# mosfet-shield-v2.net
KiCad netlist of a schematic drawn in EAGLE
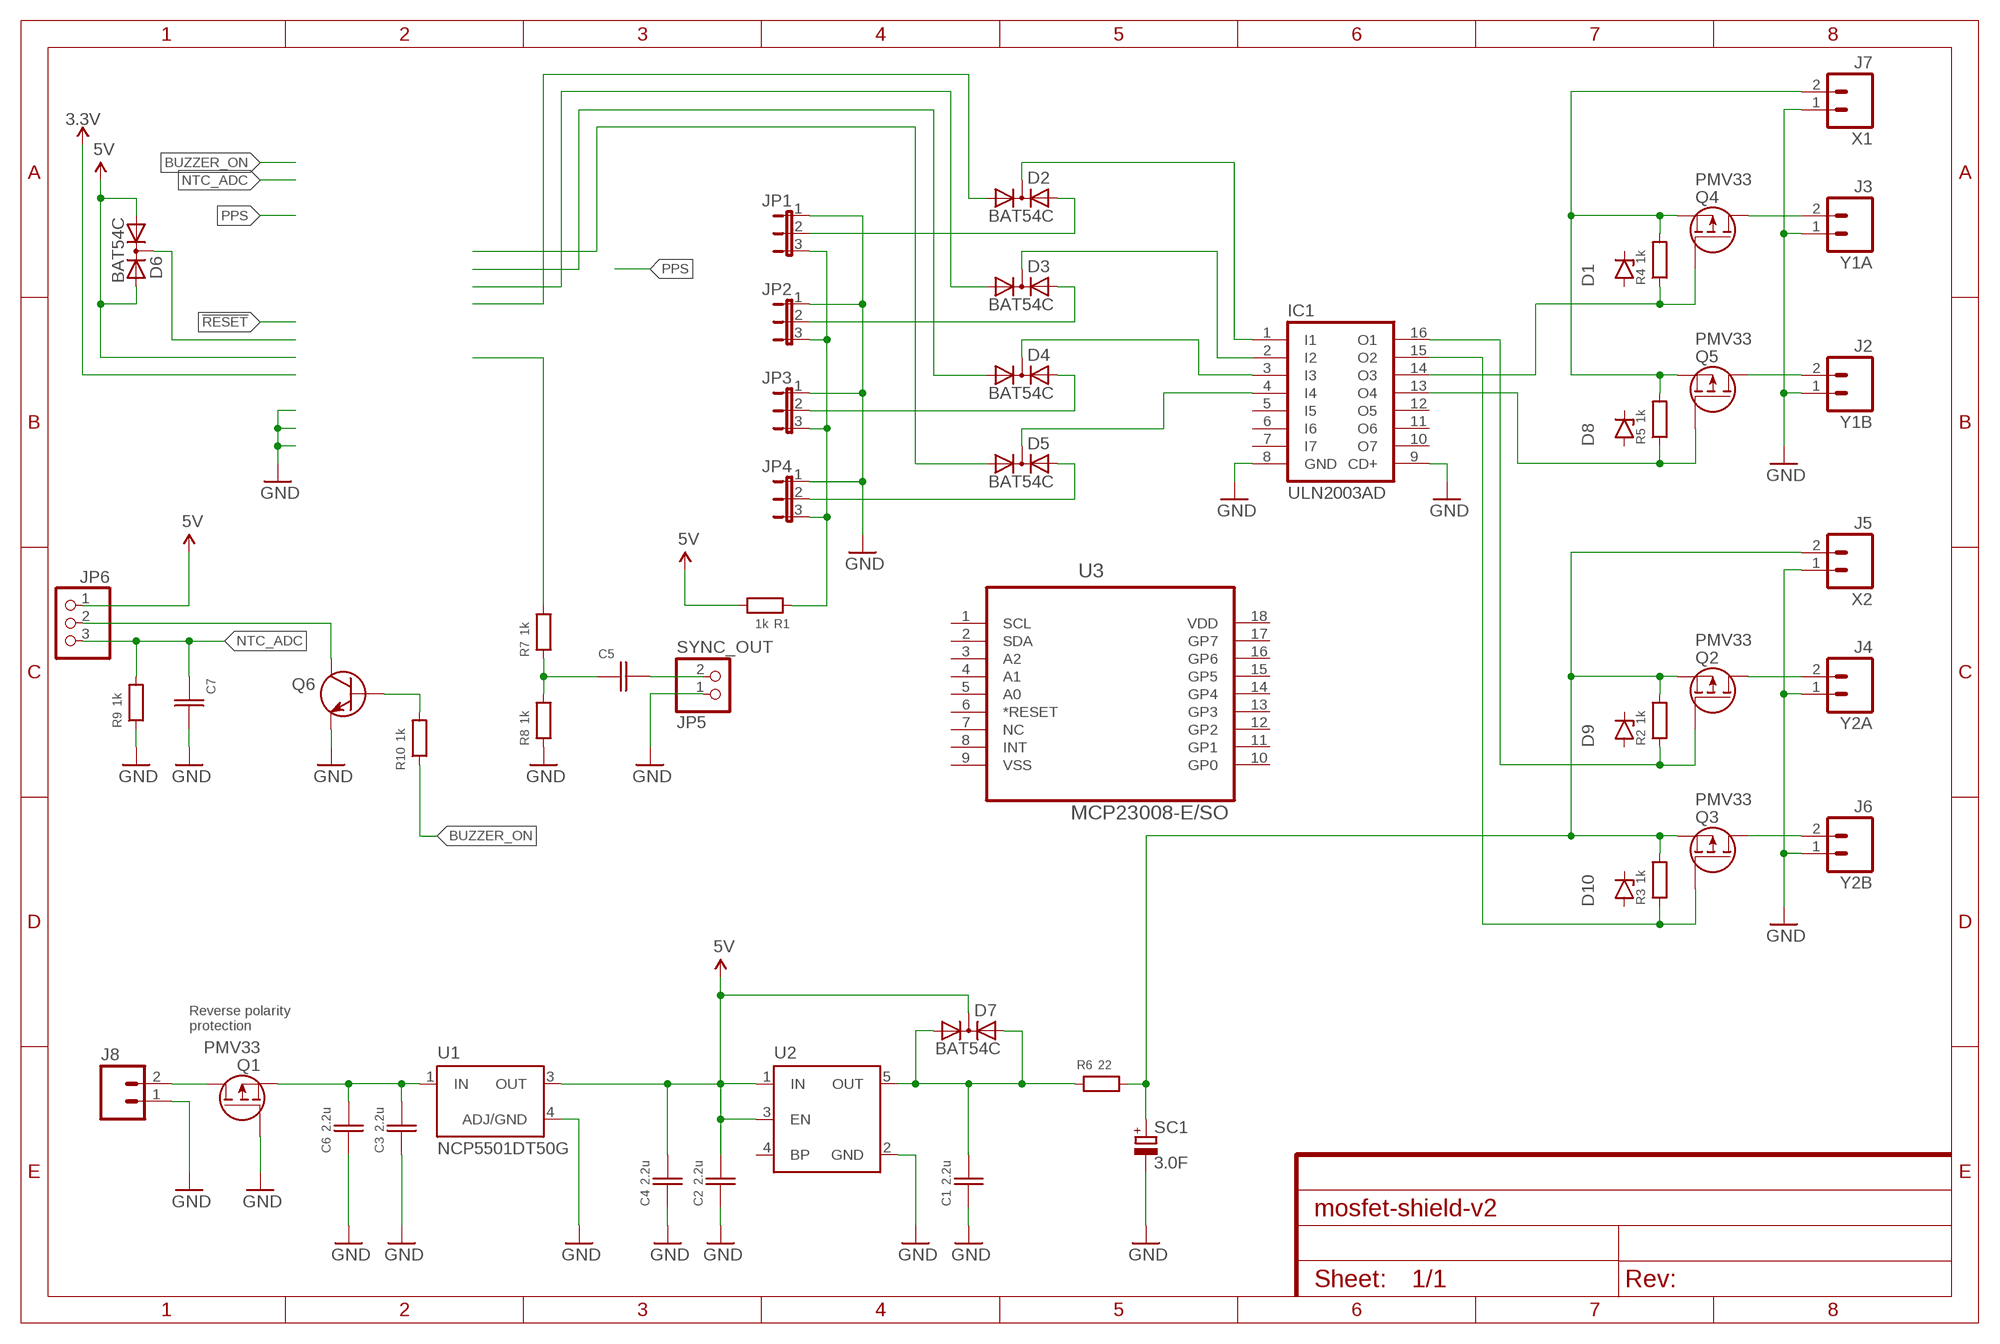
[diagram p0: schematic, sheet 1]

(export (version "E")
  (design (tool "Eeschema 10.0.6"))
  (components
    (comp (ref "C1")
      (value "2.2u")
      (footprint "eagle-import:C1206")
      (libsource (lib "eagle-import") (part "CAPACITOR_NPOL-1206"))
    )
    (comp (ref "C2")
      (value "2.2u")
      (footprint "eagle-import:C1206")
      (libsource (lib "eagle-import") (part "CAPACITOR_NPOL-1206"))
    )
    (comp (ref "C3")
      (value "2.2u")
      (footprint "eagle-import:C1206")
      (libsource (lib "eagle-import") (part "CAPACITOR_NPOL-1206"))
    )
    (comp (ref "C4")
      (value "2.2u")
      (footprint "eagle-import:C1206")
      (libsource (lib "eagle-import") (part "CAPACITOR_NPOL-1206"))
    )
    (comp (ref "C5")
      (value "CAPACITOR_NPOL-0603")
      (footprint "eagle-import:C603")
      (libsource (lib "eagle-import") (part "CAPACITOR_NPOL-0603"))
    )
    (comp (ref "C6")
      (value "2.2u")
      (footprint "eagle-import:C1206")
      (libsource (lib "eagle-import") (part "CAPACITOR_NPOL-1206"))
    )
    (comp (ref "C7")
      (value "CAPACITOR_NPOL-0603")
      (footprint "eagle-import:C603")
      (libsource (lib "eagle-import") (part "CAPACITOR_NPOL-0603"))
    )
    (comp (ref "D1")
      (value "DIODE-ZENER-SOD80")
      (footprint "eagle-import:SOD80")
      (libsource (lib "eagle-import") (part "DIODE-ZENER-SOD80"))
    )
    (comp (ref "D2")
      (value "BAT54C")
      (footprint "eagle-import:SOT23")
      (libsource (lib "eagle-import") (part "DIODE-2AC|CASOT23"))
    )
    (comp (ref "D3")
      (value "BAT54C")
      (footprint "eagle-import:SOT23")
      (libsource (lib "eagle-import") (part "DIODE-2AC|CASOT23"))
    )
    (comp (ref "D4")
      (value "BAT54C")
      (footprint "eagle-import:SOT23")
      (libsource (lib "eagle-import") (part "DIODE-2AC|CASOT23"))
    )
    (comp (ref "D5")
      (value "BAT54C")
      (footprint "eagle-import:SOT23")
      (libsource (lib "eagle-import") (part "DIODE-2AC|CASOT23"))
    )
    (comp (ref "D6")
      (value "BAT54C")
      (footprint "eagle-import:SOT23")
      (libsource (lib "eagle-import") (part "DIODE-2AC|CASOT23"))
    )
    (comp (ref "D7")
      (value "BAT54C")
      (footprint "eagle-import:SOT23")
      (libsource (lib "eagle-import") (part "DIODE-2AC|CASOT23"))
    )
    (comp (ref "D8")
      (value "DIODE-ZENER-SOD80")
      (footprint "eagle-import:SOD80")
      (libsource (lib "eagle-import") (part "DIODE-ZENER-SOD80"))
    )
    (comp (ref "D9")
      (value "DIODE-ZENER-SOD80")
      (footprint "eagle-import:SOD80")
      (libsource (lib "eagle-import") (part "DIODE-ZENER-SOD80"))
    )
    (comp (ref "D10")
      (value "DIODE-ZENER-SOD80")
      (footprint "eagle-import:SOD80")
      (libsource (lib "eagle-import") (part "DIODE-ZENER-SOD80"))
    )
    (comp (ref "IC1")
      (value "ULN2003AD")
      (footprint "eagle-import:SO16")
      (libsource (lib "eagle-import") (part "ULN2003AD"))
    )
    (comp (ref "J2")
      (value "Y1B")
      (footprint "eagle-import:SCREWTERMINAL-3.5MM-2")
      (libsource (lib "eagle-import") (part "M023.5MM"))
    )
    (comp (ref "J3")
      (value "Y1A")
      (footprint "eagle-import:SCREWTERMINAL-3.5MM-2")
      (libsource (lib "eagle-import") (part "M023.5MM"))
    )
    (comp (ref "J4")
      (value "Y2A")
      (footprint "eagle-import:SCREWTERMINAL-3.5MM-2")
      (libsource (lib "eagle-import") (part "M023.5MM"))
    )
    (comp (ref "J5")
      (value "X2")
      (footprint "eagle-import:SCREWTERMINAL-3.5MM-2")
      (libsource (lib "eagle-import") (part "M023.5MM"))
    )
    (comp (ref "J6")
      (value "Y2B")
      (footprint "eagle-import:SCREWTERMINAL-3.5MM-2")
      (libsource (lib "eagle-import") (part "M023.5MM"))
    )
    (comp (ref "J7")
      (value "X1")
      (footprint "eagle-import:SCREWTERMINAL-3.5MM-2")
      (libsource (lib "eagle-import") (part "M023.5MM"))
    )
    (comp (ref "J8")
      (value "M023.5MM")
      (footprint "eagle-import:SCREWTERMINAL-3.5MM-2")
      (libsource (lib "eagle-import") (part "M023.5MM"))
    )
    (comp (ref "JP1")
      (value "JP2E")
      (footprint "eagle-import:JP2")
      (libsource (lib "eagle-import") (part "JP2E"))
    )
    (comp (ref "JP2")
      (value "JP2E")
      (footprint "eagle-import:JP2")
      (libsource (lib "eagle-import") (part "JP2E"))
    )
    (comp (ref "JP3")
      (value "JP2E")
      (footprint "eagle-import:JP2")
      (libsource (lib "eagle-import") (part "JP2E"))
    )
    (comp (ref "JP4")
      (value "JP2E")
      (footprint "eagle-import:JP2")
      (libsource (lib "eagle-import") (part "JP2E"))
    )
    (comp (ref "JP5")
      (value "SYNC_OUT")
      (footprint "eagle-import:1X02")
      (libsource (lib "eagle-import") (part "PINHD-1X2"))
    )
    (comp (ref "JP6")
      (value "PINHD-1X3")
      (footprint "eagle-import:1X03")
      (libsource (lib "eagle-import") (part "PINHD-1X3"))
    )
    (comp (ref "Q1")
      (value "PMV33")
      (footprint "eagle-import:SOT23-3")
      (libsource (lib "eagle-import") (part "MOSFET-P-SOT23-3"))
    )
    (comp (ref "Q2")
      (value "PMV33")
      (footprint "eagle-import:SOT23-3")
      (libsource (lib "eagle-import") (part "MOSFET-P-SOT23-3"))
    )
    (comp (ref "Q3")
      (value "PMV33")
      (footprint "eagle-import:SOT23-3")
      (libsource (lib "eagle-import") (part "MOSFET-P-SOT23-3"))
    )
    (comp (ref "Q4")
      (value "PMV33")
      (footprint "eagle-import:SOT23-3")
      (libsource (lib "eagle-import") (part "MOSFET-P-SOT23-3"))
    )
    (comp (ref "Q5")
      (value "PMV33")
      (footprint "eagle-import:SOT23-3")
      (libsource (lib "eagle-import") (part "MOSFET-P-SOT23-3"))
    )
    (comp (ref "Q6")
      (value "BJT-NPN-SOT23-3")
      (footprint "eagle-import:SOT23-3")
      (libsource (lib "eagle-import") (part "BJT-NPN-SOT23-3"))
    )
    (comp (ref "R1")
      (value "1k")
      (footprint "eagle-import:R0603")
      (libsource (lib "eagle-import") (part "RESISTOR-0603"))
    )
    (comp (ref "R2")
      (value "1k")
      (footprint "eagle-import:R0603")
      (libsource (lib "eagle-import") (part "RESISTOR-0603"))
    )
    (comp (ref "R3")
      (value "1k")
      (footprint "eagle-import:R0603")
      (libsource (lib "eagle-import") (part "RESISTOR-0603"))
    )
    (comp (ref "R4")
      (value "1k")
      (footprint "eagle-import:R0603")
      (libsource (lib "eagle-import") (part "RESISTOR-0603"))
    )
    (comp (ref "R5")
      (value "1k")
      (footprint "eagle-import:R0603")
      (libsource (lib "eagle-import") (part "RESISTOR-0603"))
    )
    (comp (ref "R6")
      (value "22")
      (footprint "eagle-import:R0603")
      (libsource (lib "eagle-import") (part "RESISTOR-0603"))
    )
    (comp (ref "R7")
      (value "1k")
      (footprint "eagle-import:R0603")
      (libsource (lib "eagle-import") (part "RESISTOR-0603"))
    )
    (comp (ref "R8")
      (value "1k")
      (footprint "eagle-import:R0603")
      (libsource (lib "eagle-import") (part "RESISTOR-0603"))
    )
    (comp (ref "R9")
      (value "1k")
      (footprint "eagle-import:R0603")
      (libsource (lib "eagle-import") (part "RESISTOR-0603"))
    )
    (comp (ref "R10")
      (value "1k")
      (footprint "eagle-import:R0603")
      (libsource (lib "eagle-import") (part "RESISTOR-0603"))
    )
    (comp (ref "SC1")
      (value "3.0F")
      (footprint "eagle-import:E3,5-8")
      (libsource (lib "eagle-import") (part "CPOL-EUE3.5-8"))
    )
    (comp (ref "U1")
      (value "NCP5501DT50G")
      (footprint "eagle-import:DPAK")
      (libsource (lib "eagle-import") (part "VREG-3PIN-DPAK"))
    )
    (comp (ref "U2")
      (value "VREG-5PIN-SOT23")
      (footprint "eagle-import:SOT23-5")
      (libsource (lib "eagle-import") (part "VREG-5PIN-SOT23"))
    )
    (comp (ref "U3")
      (value "MCP23008-E/SO")
      (footprint "eagle-import:SOIC127P1030X265-18N")
      (libsource (lib "eagle-import") (part "MCP23008-E/SO"))
    )
  )
  (nets
    (net (code "1") (name "/VDD") (class "Default")
      (node (ref "U3") (pin "18") (pinfunction "VDD_18") (pintype "power_in"))
    )
    (net (code "4") (name "5V") (class "Default")
      (node (ref "C2") (pin "2") (pinfunction "2_2") (pintype "passive"))
      (node (ref "C4") (pin "2") (pinfunction "2_2") (pintype "passive"))
      (node (ref "D6") (pin "1") (pinfunction "A1_1") (pintype "passive"))
      (node (ref "D6") (pin "2") (pinfunction "A2_2") (pintype "passive"))
      (node (ref "D7") (pin "3") (pinfunction "C_3") (pintype "passive"))
      (node (ref "JP6") (pin "1") (pinfunction "1_1") (pintype "passive"))
      (node (ref "R1") (pin "2") (pinfunction "2_2") (pintype "passive"))
      (node (ref "U1") (pin "3") (pinfunction "OUT_3") (pintype "bidirectional"))
      (node (ref "U2") (pin "1") (pinfunction "IN_1") (pintype "bidirectional"))
      (node (ref "U2") (pin "3") (pinfunction "EN_3") (pintype "bidirectional"))
    )
    (net (code "5") (name "BUZZER_ON") (class "Default")
      (node (ref "R10") (pin "1") (pinfunction "1_1") (pintype "passive"))
    )
    (net (code "6") (name "GND") (class "Default")
      (node (ref "C1") (pin "1") (pinfunction "1_1") (pintype "passive"))
      (node (ref "C2") (pin "1") (pinfunction "1_1") (pintype "passive"))
      (node (ref "C3") (pin "1") (pinfunction "1_1") (pintype "passive"))
      (node (ref "C4") (pin "1") (pinfunction "1_1") (pintype "passive"))
      (node (ref "C6") (pin "1") (pinfunction "1_1") (pintype "passive"))
      (node (ref "C7") (pin "2") (pinfunction "2_2") (pintype "passive"))
      (node (ref "IC1") (pin "8") (pinfunction "GND_8") (pintype "power_in"))
      (node (ref "IC1") (pin "9") (pinfunction "CD+_9") (pintype "passive"))
      (node (ref "J2") (pin "1") (pinfunction "1_1") (pintype "passive"))
      (node (ref "J3") (pin "1") (pinfunction "1_1") (pintype "passive"))
      (node (ref "J4") (pin "1") (pinfunction "1_1") (pintype "passive"))
      (node (ref "J5") (pin "1") (pinfunction "1_1") (pintype "passive"))
      (node (ref "J6") (pin "1") (pinfunction "1_1") (pintype "passive"))
      (node (ref "J7") (pin "1") (pinfunction "1_1") (pintype "passive"))
      (node (ref "J8") (pin "1") (pinfunction "1_1") (pintype "passive"))
      (node (ref "JP1") (pin "1") (pinfunction "1_1") (pintype "passive"))
      (node (ref "JP2") (pin "1") (pinfunction "1_1") (pintype "passive"))
      (node (ref "JP3") (pin "1") (pinfunction "1_1") (pintype "passive"))
      (node (ref "JP4") (pin "1") (pinfunction "1_1") (pintype "passive"))
      (node (ref "JP5") (pin "1") (pinfunction "1_1") (pintype "passive"))
      (node (ref "Q1") (pin "1") (pinfunction "G_1") (pintype "passive"))
      (node (ref "Q6") (pin "2") (pinfunction "E_2") (pintype "passive"))
      (node (ref "R8") (pin "1") (pinfunction "1_1") (pintype "passive"))
      (node (ref "R9") (pin "1") (pinfunction "1_1") (pintype "passive"))
      (node (ref "SC1") (pin "-") (pinfunction "-_-") (pintype "passive"))
      (node (ref "U1") (pin "4") (pinfunction "ADJ/GND_4") (pintype "bidirectional"))
      (node (ref "U2") (pin "2") (pinfunction "GND_2") (pintype "bidirectional"))
    )
    (net (code "7") (name "NTC_ADC") (class "Default")
      (node (ref "C7") (pin "1") (pinfunction "1_1") (pintype "passive"))
      (node (ref "JP6") (pin "3") (pinfunction "3_3") (pintype "passive"))
      (node (ref "R9") (pin "2") (pinfunction "2_2") (pintype "passive"))
    )
    (net (code "8") (name "Net-(C5-Pad1)") (class "Default")
      (node (ref "C5") (pin "1") (pinfunction "1_1") (pintype "passive"))
      (node (ref "R7") (pin "1") (pinfunction "1_1") (pintype "passive"))
      (node (ref "R8") (pin "2") (pinfunction "2_2") (pintype "passive"))
    )
    (net (code "9") (name "Net-(C5-Pad2)") (class "Default")
      (node (ref "C5") (pin "2") (pinfunction "2_2") (pintype "passive"))
      (node (ref "JP5") (pin "2") (pinfunction "2_2") (pintype "passive"))
    )
    (net (code "10") (name "Net-(D2-A2)") (class "Default")
      (node (ref "D2") (pin "2") (pinfunction "A2_2") (pintype "passive"))
      (node (ref "JP1") (pin "2") (pinfunction "2_2") (pintype "passive"))
    )
    (net (code "11") (name "Net-(D2-C)") (class "Default")
      (node (ref "D2") (pin "3") (pinfunction "C_3") (pintype "passive"))
      (node (ref "IC1") (pin "1") (pinfunction "I1_1") (pintype "input"))
    )
    (net (code "12") (name "Net-(D3-A2)") (class "Default")
      (node (ref "D3") (pin "2") (pinfunction "A2_2") (pintype "passive"))
      (node (ref "JP2") (pin "2") (pinfunction "2_2") (pintype "passive"))
    )
    (net (code "13") (name "Net-(D3-C)") (class "Default")
      (node (ref "D3") (pin "3") (pinfunction "C_3") (pintype "passive"))
      (node (ref "IC1") (pin "2") (pinfunction "I2_2") (pintype "input"))
    )
    (net (code "14") (name "Net-(D4-A2)") (class "Default")
      (node (ref "D4") (pin "2") (pinfunction "A2_2") (pintype "passive"))
      (node (ref "JP3") (pin "2") (pinfunction "2_2") (pintype "passive"))
    )
    (net (code "15") (name "Net-(D4-C)") (class "Default")
      (node (ref "D4") (pin "3") (pinfunction "C_3") (pintype "passive"))
      (node (ref "IC1") (pin "3") (pinfunction "I3_3") (pintype "input"))
    )
    (net (code "16") (name "Net-(D5-A2)") (class "Default")
      (node (ref "D5") (pin "2") (pinfunction "A2_2") (pintype "passive"))
      (node (ref "JP4") (pin "2") (pinfunction "2_2") (pintype "passive"))
    )
    (net (code "17") (name "Net-(D5-C)") (class "Default")
      (node (ref "D5") (pin "3") (pinfunction "C_3") (pintype "passive"))
      (node (ref "IC1") (pin "4") (pinfunction "I4_4") (pintype "input"))
    )
    (net (code "18") (name "Net-(D7-A1)") (class "Default")
      (node (ref "C1") (pin "2") (pinfunction "2_2") (pintype "passive"))
      (node (ref "D7") (pin "1") (pinfunction "A1_1") (pintype "passive"))
      (node (ref "D7") (pin "2") (pinfunction "A2_2") (pintype "passive"))
      (node (ref "R6") (pin "1") (pinfunction "1_1") (pintype "passive"))
      (node (ref "U2") (pin "5") (pinfunction "OUT_5") (pintype "bidirectional"))
    )
    (net (code "19") (name "Net-(IC1-O1)") (class "Default")
      (node (ref "IC1") (pin "16") (pinfunction "O1_16") (pintype "open_collector"))
      (node (ref "Q2") (pin "1") (pinfunction "G_1") (pintype "passive"))
      (node (ref "R2") (pin "1") (pinfunction "1_1") (pintype "passive"))
    )
    (net (code "20") (name "Net-(IC1-O2)") (class "Default")
      (node (ref "IC1") (pin "15") (pinfunction "O2_15") (pintype "open_collector"))
      (node (ref "Q3") (pin "1") (pinfunction "G_1") (pintype "passive"))
      (node (ref "R3") (pin "1") (pinfunction "1_1") (pintype "passive"))
    )
    (net (code "21") (name "Net-(IC1-O3)") (class "Default")
      (node (ref "IC1") (pin "14") (pinfunction "O3_14") (pintype "open_collector"))
      (node (ref "Q4") (pin "1") (pinfunction "G_1") (pintype "passive"))
      (node (ref "R4") (pin "1") (pinfunction "1_1") (pintype "passive"))
    )
    (net (code "22") (name "Net-(IC1-O4)") (class "Default")
      (node (ref "IC1") (pin "13") (pinfunction "O4_13") (pintype "open_collector"))
      (node (ref "Q5") (pin "1") (pinfunction "G_1") (pintype "passive"))
      (node (ref "R5") (pin "1") (pinfunction "1_1") (pintype "passive"))
    )
    (net (code "23") (name "Net-(JP1-Pad3)") (class "Default")
      (node (ref "JP1") (pin "3") (pinfunction "3_3") (pintype "passive"))
      (node (ref "JP2") (pin "3") (pinfunction "3_3") (pintype "passive"))
      (node (ref "JP3") (pin "3") (pinfunction "3_3") (pintype "passive"))
      (node (ref "JP4") (pin "3") (pinfunction "3_3") (pintype "passive"))
      (node (ref "R1") (pin "1") (pinfunction "1_1") (pintype "passive"))
    )
    (net (code "24") (name "Net-(Q1-D)") (class "Default")
      (node (ref "J8") (pin "2") (pinfunction "2_2") (pintype "passive"))
      (node (ref "Q1") (pin "3") (pinfunction "D_3") (pintype "passive"))
    )
    (net (code "25") (name "Net-(Q1-S)") (class "Default")
      (node (ref "C3") (pin "2") (pinfunction "2_2") (pintype "passive"))
      (node (ref "C6") (pin "2") (pinfunction "2_2") (pintype "passive"))
      (node (ref "Q1") (pin "2") (pinfunction "S_2") (pintype "passive"))
      (node (ref "U1") (pin "1") (pinfunction "IN_1") (pintype "bidirectional"))
    )
    (net (code "26") (name "Net-(Q2-D)") (class "Default")
      (node (ref "J4") (pin "2") (pinfunction "2_2") (pintype "passive"))
      (node (ref "Q2") (pin "3") (pinfunction "D_3") (pintype "passive"))
    )
    (net (code "27") (name "Net-(Q2-S)") (class "Default")
      (node (ref "J5") (pin "2") (pinfunction "2_2") (pintype "passive"))
      (node (ref "Q2") (pin "2") (pinfunction "S_2") (pintype "passive"))
      (node (ref "Q3") (pin "2") (pinfunction "S_2") (pintype "passive"))
      (node (ref "R2") (pin "2") (pinfunction "2_2") (pintype "passive"))
      (node (ref "R3") (pin "2") (pinfunction "2_2") (pintype "passive"))
      (node (ref "R6") (pin "2") (pinfunction "2_2") (pintype "passive"))
      (node (ref "SC1") (pin "+") (pinfunction "+_+") (pintype "passive"))
    )
    (net (code "28") (name "Net-(Q3-D)") (class "Default")
      (node (ref "J6") (pin "2") (pinfunction "2_2") (pintype "passive"))
      (node (ref "Q3") (pin "3") (pinfunction "D_3") (pintype "passive"))
    )
    (net (code "29") (name "Net-(Q4-D)") (class "Default")
      (node (ref "J3") (pin "2") (pinfunction "2_2") (pintype "passive"))
      (node (ref "Q4") (pin "3") (pinfunction "D_3") (pintype "passive"))
    )
    (net (code "30") (name "Net-(Q4-S)") (class "Default")
      (node (ref "J7") (pin "2") (pinfunction "2_2") (pintype "passive"))
      (node (ref "Q4") (pin "2") (pinfunction "S_2") (pintype "passive"))
      (node (ref "Q5") (pin "2") (pinfunction "S_2") (pintype "passive"))
      (node (ref "R4") (pin "2") (pinfunction "2_2") (pintype "passive"))
      (node (ref "R5") (pin "2") (pinfunction "2_2") (pintype "passive"))
    )
    (net (code "31") (name "Net-(Q5-D)") (class "Default")
      (node (ref "J2") (pin "2") (pinfunction "2_2") (pintype "passive"))
      (node (ref "Q5") (pin "3") (pinfunction "D_3") (pintype "passive"))
    )
    (net (code "32") (name "Net-(Q6-B)") (class "Default")
      (node (ref "Q6") (pin "1") (pinfunction "B_1") (pintype "passive"))
      (node (ref "R10") (pin "2") (pinfunction "2_2") (pintype "passive"))
    )
    (net (code "33") (name "Net-(Q6-C)") (class "Default")
      (node (ref "JP6") (pin "2") (pinfunction "2_2") (pintype "passive"))
      (node (ref "Q6") (pin "3") (pinfunction "C_3") (pintype "passive"))
    )
    (net (code "35") (name "unconnected-(D1-PadA)") (class "Default")
      (node (ref "D1") (pin "A") (pinfunction "A_A") (pintype "passive"))
    )
    (net (code "36") (name "unconnected-(D1-PadC)") (class "Default")
      (node (ref "D1") (pin "C") (pinfunction "C_C") (pintype "passive"))
    )
    (net (code "37") (name "unconnected-(D2-A1-Pad1)") (class "Default")
      (node (ref "D2") (pin "1") (pinfunction "A1_1") (pintype "passive"))
    )
    (net (code "38") (name "unconnected-(D3-A1-Pad1)") (class "Default")
      (node (ref "D3") (pin "1") (pinfunction "A1_1") (pintype "passive"))
    )
    (net (code "39") (name "unconnected-(D4-A1-Pad1)") (class "Default")
      (node (ref "D4") (pin "1") (pinfunction "A1_1") (pintype "passive"))
    )
    (net (code "40") (name "unconnected-(D5-A1-Pad1)") (class "Default")
      (node (ref "D5") (pin "1") (pinfunction "A1_1") (pintype "passive"))
    )
    (net (code "41") (name "unconnected-(D6-C-Pad3)") (class "Default")
      (node (ref "D6") (pin "3") (pinfunction "C_3") (pintype "passive"))
    )
    (net (code "42") (name "unconnected-(D8-PadA)") (class "Default")
      (node (ref "D8") (pin "A") (pinfunction "A_A") (pintype "passive"))
    )
    (net (code "43") (name "unconnected-(D8-PadC)") (class "Default")
      (node (ref "D8") (pin "C") (pinfunction "C_C") (pintype "passive"))
    )
    (net (code "44") (name "unconnected-(D9-PadA)") (class "Default")
      (node (ref "D9") (pin "A") (pinfunction "A_A") (pintype "passive"))
    )
    (net (code "45") (name "unconnected-(D9-PadC)") (class "Default")
      (node (ref "D9") (pin "C") (pinfunction "C_C") (pintype "passive"))
    )
    (net (code "46") (name "unconnected-(D10-PadA)") (class "Default")
      (node (ref "D10") (pin "A") (pinfunction "A_A") (pintype "passive"))
    )
    (net (code "47") (name "unconnected-(D10-PadC)") (class "Default")
      (node (ref "D10") (pin "C") (pinfunction "C_C") (pintype "passive"))
    )
    (net (code "48") (name "unconnected-(IC1-I5-Pad5)") (class "Default")
      (node (ref "IC1") (pin "5") (pinfunction "I5_5") (pintype "input"))
    )
    (net (code "49") (name "unconnected-(IC1-I6-Pad6)") (class "Default")
      (node (ref "IC1") (pin "6") (pinfunction "I6_6") (pintype "input"))
    )
    (net (code "50") (name "unconnected-(IC1-I7-Pad7)") (class "Default")
      (node (ref "IC1") (pin "7") (pinfunction "I7_7") (pintype "input"))
    )
    (net (code "51") (name "unconnected-(IC1-O5-Pad12)") (class "Default")
      (node (ref "IC1") (pin "12") (pinfunction "O5_12") (pintype "open_collector"))
    )
    (net (code "52") (name "unconnected-(IC1-O6-Pad11)") (class "Default")
      (node (ref "IC1") (pin "11") (pinfunction "O6_11") (pintype "open_collector"))
    )
    (net (code "53") (name "unconnected-(IC1-O7-Pad10)") (class "Default")
      (node (ref "IC1") (pin "10") (pinfunction "O7_10") (pintype "open_collector"))
    )
    (net (code "54") (name "unconnected-(R7-Pad2)") (class "Default")
      (node (ref "R7") (pin "2") (pinfunction "2_2") (pintype "passive"))
    )
    (net (code "55") (name "unconnected-(U2-BP-Pad4)") (class "Default")
      (node (ref "U2") (pin "4") (pinfunction "BP_4") (pintype "bidirectional"))
    )
    (net (code "56") (name "unconnected-(U3-*RESET-Pad6)") (class "Default")
      (node (ref "U3") (pin "6") (pinfunction "*RESET_6") (pintype "input"))
    )
    (net (code "57") (name "unconnected-(U3-A0-Pad5)") (class "Default")
      (node (ref "U3") (pin "5") (pinfunction "A0_5") (pintype "input"))
    )
    (net (code "58") (name "unconnected-(U3-A1-Pad4)") (class "Default")
      (node (ref "U3") (pin "4") (pinfunction "A1_4") (pintype "input"))
    )
    (net (code "59") (name "unconnected-(U3-A2-Pad3)") (class "Default")
      (node (ref "U3") (pin "3") (pinfunction "A2_3") (pintype "passive"))
    )
    (net (code "60") (name "unconnected-(U3-GP0-Pad10)") (class "Default")
      (node (ref "U3") (pin "10") (pinfunction "GP0_10") (pintype "passive"))
    )
    (net (code "61") (name "unconnected-(U3-GP1-Pad11)") (class "Default")
      (node (ref "U3") (pin "11") (pinfunction "GP1_11") (pintype "passive"))
    )
    (net (code "62") (name "unconnected-(U3-GP2-Pad12)") (class "Default")
      (node (ref "U3") (pin "12") (pinfunction "GP2_12") (pintype "passive"))
    )
    (net (code "63") (name "unconnected-(U3-GP3-Pad13)") (class "Default")
      (node (ref "U3") (pin "13") (pinfunction "GP3_13") (pintype "passive"))
    )
    (net (code "64") (name "unconnected-(U3-GP4-Pad14)") (class "Default")
      (node (ref "U3") (pin "14") (pinfunction "GP4_14") (pintype "passive"))
    )
    (net (code "65") (name "unconnected-(U3-GP5-Pad15)") (class "Default")
      (node (ref "U3") (pin "15") (pinfunction "GP5_15") (pintype "passive"))
    )
    (net (code "66") (name "unconnected-(U3-GP6-Pad16)") (class "Default")
      (node (ref "U3") (pin "16") (pinfunction "GP6_16") (pintype "passive"))
    )
    (net (code "67") (name "unconnected-(U3-GP7-Pad17)") (class "Default")
      (node (ref "U3") (pin "17") (pinfunction "GP7_17") (pintype "passive"))
    )
    (net (code "68") (name "unconnected-(U3-INT-Pad8)") (class "Default")
      (node (ref "U3") (pin "8") (pinfunction "INT_8") (pintype "output"))
    )
    (net (code "69") (name "unconnected-(U3-NC-Pad7)") (class "Default")
      (node (ref "U3") (pin "7") (pinfunction "NC_7") (pintype "input"))
    )
    (net (code "70") (name "unconnected-(U3-SCL-Pad1)") (class "Default")
      (node (ref "U3") (pin "1") (pinfunction "SCL_1") (pintype "input"))
    )
    (net (code "71") (name "unconnected-(U3-SDA-Pad2)") (class "Default")
      (node (ref "U3") (pin "2") (pinfunction "SDA_2") (pintype "passive"))
    )
    (net (code "72") (name "unconnected-(U3-VSS-Pad9)") (class "Default")
      (node (ref "U3") (pin "9") (pinfunction "VSS_9") (pintype "passive"))
    )
  )
)
